# 16X2LCD_SIMPLE_SPI.net
KiCad netlist of a schematic drawn in EAGLE
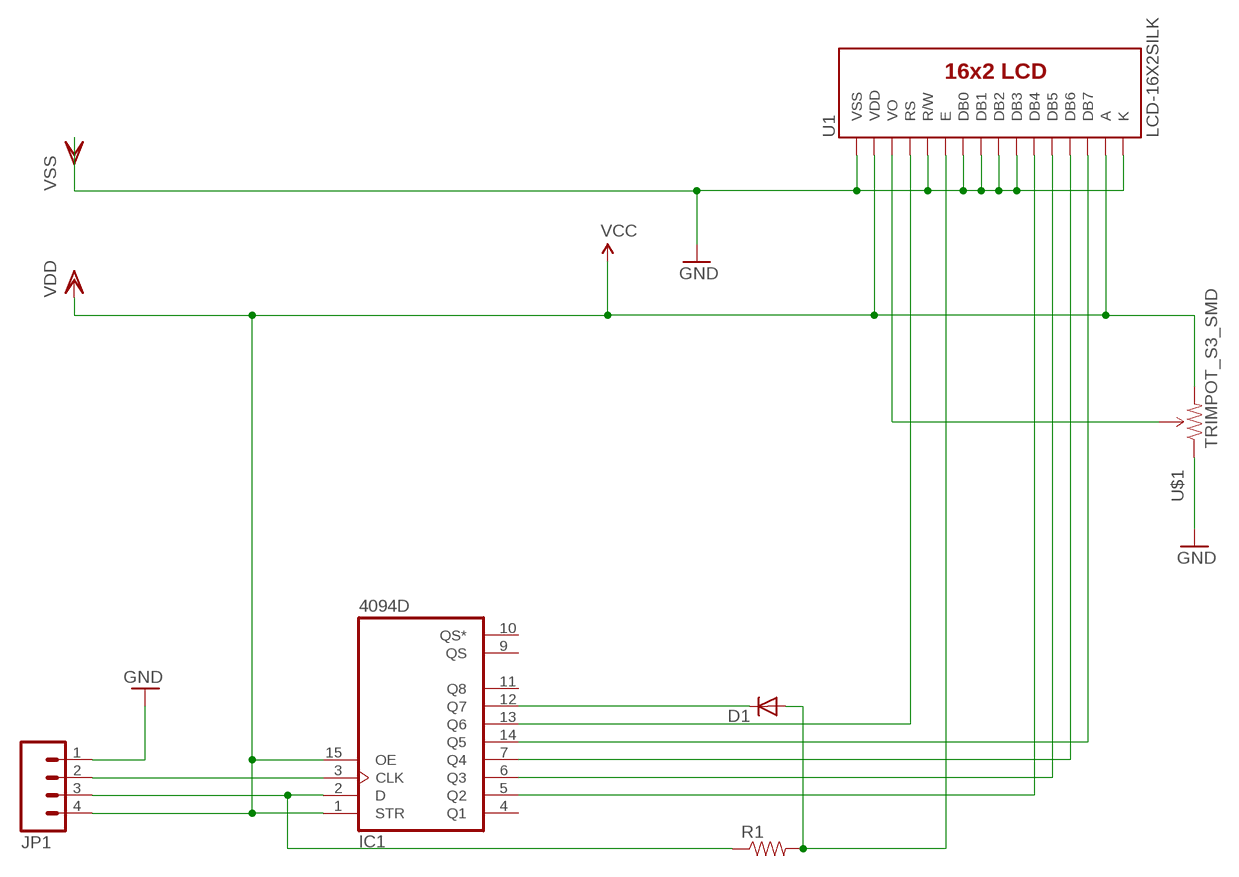
[diagram p0: schematic, sheet 1]

(export (version "E")
  (design (tool "Eeschema 10.0.6"))
  (components
    (comp (ref "D1")
      (value "DIODESMA")
      (footprint "eagle-import:SMA-DIODE")
      (libsource (lib "eagle-import") (part "DIODESMA"))
    )
    (comp (ref "IC1")
      (value "4094D")
      (footprint "eagle-import:SO16")
      (libsource (lib "eagle-import") (part "4094D"))
    )
    (comp (ref "JP1")
      (value "M04PTH")
      (footprint "eagle-import:1X04")
      (libsource (lib "eagle-import") (part "M04PTH"))
    )
    (comp (ref "R1")
      (value "RESISTOR1206")
      (footprint "eagle-import:1206")
      (libsource (lib "eagle-import") (part "RESISTOR1206"))
    )
    (comp (ref "U$1")
      (value "TRIMPOT_S3_SMD")
      (footprint "eagle-import:TRIMPOT_S3_SMD")
      (libsource (lib "eagle-import") (part "TRIMPOT_S3_SMD"))
    )
    (comp (ref "U1")
      (value "LCD-16X2SILK")
      (footprint "eagle-import:LCD-16X2")
      (libsource (lib "eagle-import") (part "LCD-16X2SILK"))
    )
  )
  (nets
    (net (code "1") (name "GND") (class "Default")
      (node (ref "JP1") (pin "1") (pinfunction "1_1") (pintype "passive"))
      (node (ref "U$1") (pin "P$1") (pinfunction "CCW_P$1") (pintype "passive"))
      (node (ref "U1") (pin "1") (pinfunction "VSS_1") (pintype "power_in"))
      (node (ref "U1") (pin "10") (pinfunction "DB3_10") (pintype "bidirectional"))
      (node (ref "U1") (pin "16") (pinfunction "K_16") (pintype "power_in"))
      (node (ref "U1") (pin "5") (pinfunction "R/W_5") (pintype "input"))
      (node (ref "U1") (pin "7") (pinfunction "DB0_7") (pintype "bidirectional"))
      (node (ref "U1") (pin "8") (pinfunction "DB1_8") (pintype "bidirectional"))
      (node (ref "U1") (pin "9") (pinfunction "DB2_9") (pintype "bidirectional"))
    )
    (net (code "2") (name "Net-(IC1A-CLK)") (class "Default")
      (node (ref "IC1") (pin "3") (pinfunction "CLK_3") (pintype "input"))
      (node (ref "JP1") (pin "2") (pinfunction "2_2") (pintype "passive"))
    )
    (net (code "3") (name "Net-(IC1A-D)") (class "Default")
      (node (ref "IC1") (pin "2") (pinfunction "D_2") (pintype "input"))
      (node (ref "JP1") (pin "3") (pinfunction "3_3") (pintype "passive"))
      (node (ref "R1") (pin "1") (pinfunction "1_1") (pintype "passive"))
    )
    (net (code "4") (name "Net-(IC1A-Q2)") (class "Default")
      (node (ref "IC1") (pin "5") (pinfunction "Q2_5") (pintype "output"))
      (node (ref "U1") (pin "11") (pinfunction "DB4_11") (pintype "bidirectional"))
    )
    (net (code "5") (name "Net-(IC1A-Q3)") (class "Default")
      (node (ref "IC1") (pin "6") (pinfunction "Q3_6") (pintype "output"))
      (node (ref "U1") (pin "12") (pinfunction "DB5_12") (pintype "bidirectional"))
    )
    (net (code "6") (name "Net-(IC1A-Q4)") (class "Default")
      (node (ref "IC1") (pin "7") (pinfunction "Q4_7") (pintype "output"))
      (node (ref "U1") (pin "13") (pinfunction "DB6_13") (pintype "bidirectional"))
    )
    (net (code "7") (name "Net-(IC1A-Q5)") (class "Default")
      (node (ref "IC1") (pin "14") (pinfunction "Q5_14") (pintype "output"))
      (node (ref "U1") (pin "14") (pinfunction "DB7_14") (pintype "bidirectional"))
    )
    (net (code "8") (name "Net-(IC1A-Q6)") (class "Default")
      (node (ref "IC1") (pin "13") (pinfunction "Q6_13") (pintype "output"))
      (node (ref "U1") (pin "4") (pinfunction "RS_4") (pintype "input"))
    )
    (net (code "9") (name "Net-(IC1A-Q7)") (class "Default")
      (node (ref "D1") (pin "C") (pinfunction "C_C") (pintype "passive"))
      (node (ref "IC1") (pin "12") (pinfunction "Q7_12") (pintype "output"))
    )
    (net (code "10") (name "Net-(U$1-WIPER)") (class "Default")
      (node (ref "U$1") (pin "P$2") (pinfunction "WIPER_P$2") (pintype "passive"))
      (node (ref "U1") (pin "3") (pinfunction "VO_3") (pintype "bidirectional"))
    )
    (net (code "11") (name "Net-(U1-E)") (class "Default")
      (node (ref "D1") (pin "A") (pinfunction "A_A") (pintype "passive"))
      (node (ref "R1") (pin "2") (pinfunction "2_2") (pintype "passive"))
      (node (ref "U1") (pin "6") (pinfunction "E_6") (pintype "input"))
    )
    (net (code "12") (name "VCC") (class "Default")
      (node (ref "IC1") (pin "1") (pinfunction "STR_1") (pintype "input"))
      (node (ref "IC1") (pin "15") (pinfunction "OE_15") (pintype "input"))
      (node (ref "JP1") (pin "4") (pinfunction "4_4") (pintype "passive"))
      (node (ref "U$1") (pin "P$3") (pinfunction "CW_P$3") (pintype "passive"))
      (node (ref "U1") (pin "15") (pinfunction "A_15") (pintype "power_in"))
      (node (ref "U1") (pin "2") (pinfunction "VDD_2") (pintype "power_in"))
    )
    (net (code "13") (name "unconnected-(IC1A-Q1-Pad4)") (class "Default")
      (node (ref "IC1") (pin "4") (pinfunction "Q1_4") (pintype "output"))
    )
    (net (code "14") (name "unconnected-(IC1A-Q8-Pad11)") (class "Default")
      (node (ref "IC1") (pin "11") (pinfunction "Q8_11") (pintype "output"))
    )
    (net (code "15") (name "unconnected-(IC1A-QS*-Pad10)") (class "Default")
      (node (ref "IC1") (pin "10") (pinfunction "QS*_10") (pintype "output"))
    )
    (net (code "16") (name "unconnected-(IC1A-QS-Pad9)") (class "Default")
      (node (ref "IC1") (pin "9") (pinfunction "QS_9") (pintype "output"))
    )
  )
)
